# SparkX_smol_LiPo_Power.net
KiCad netlist of a schematic drawn in EAGLE
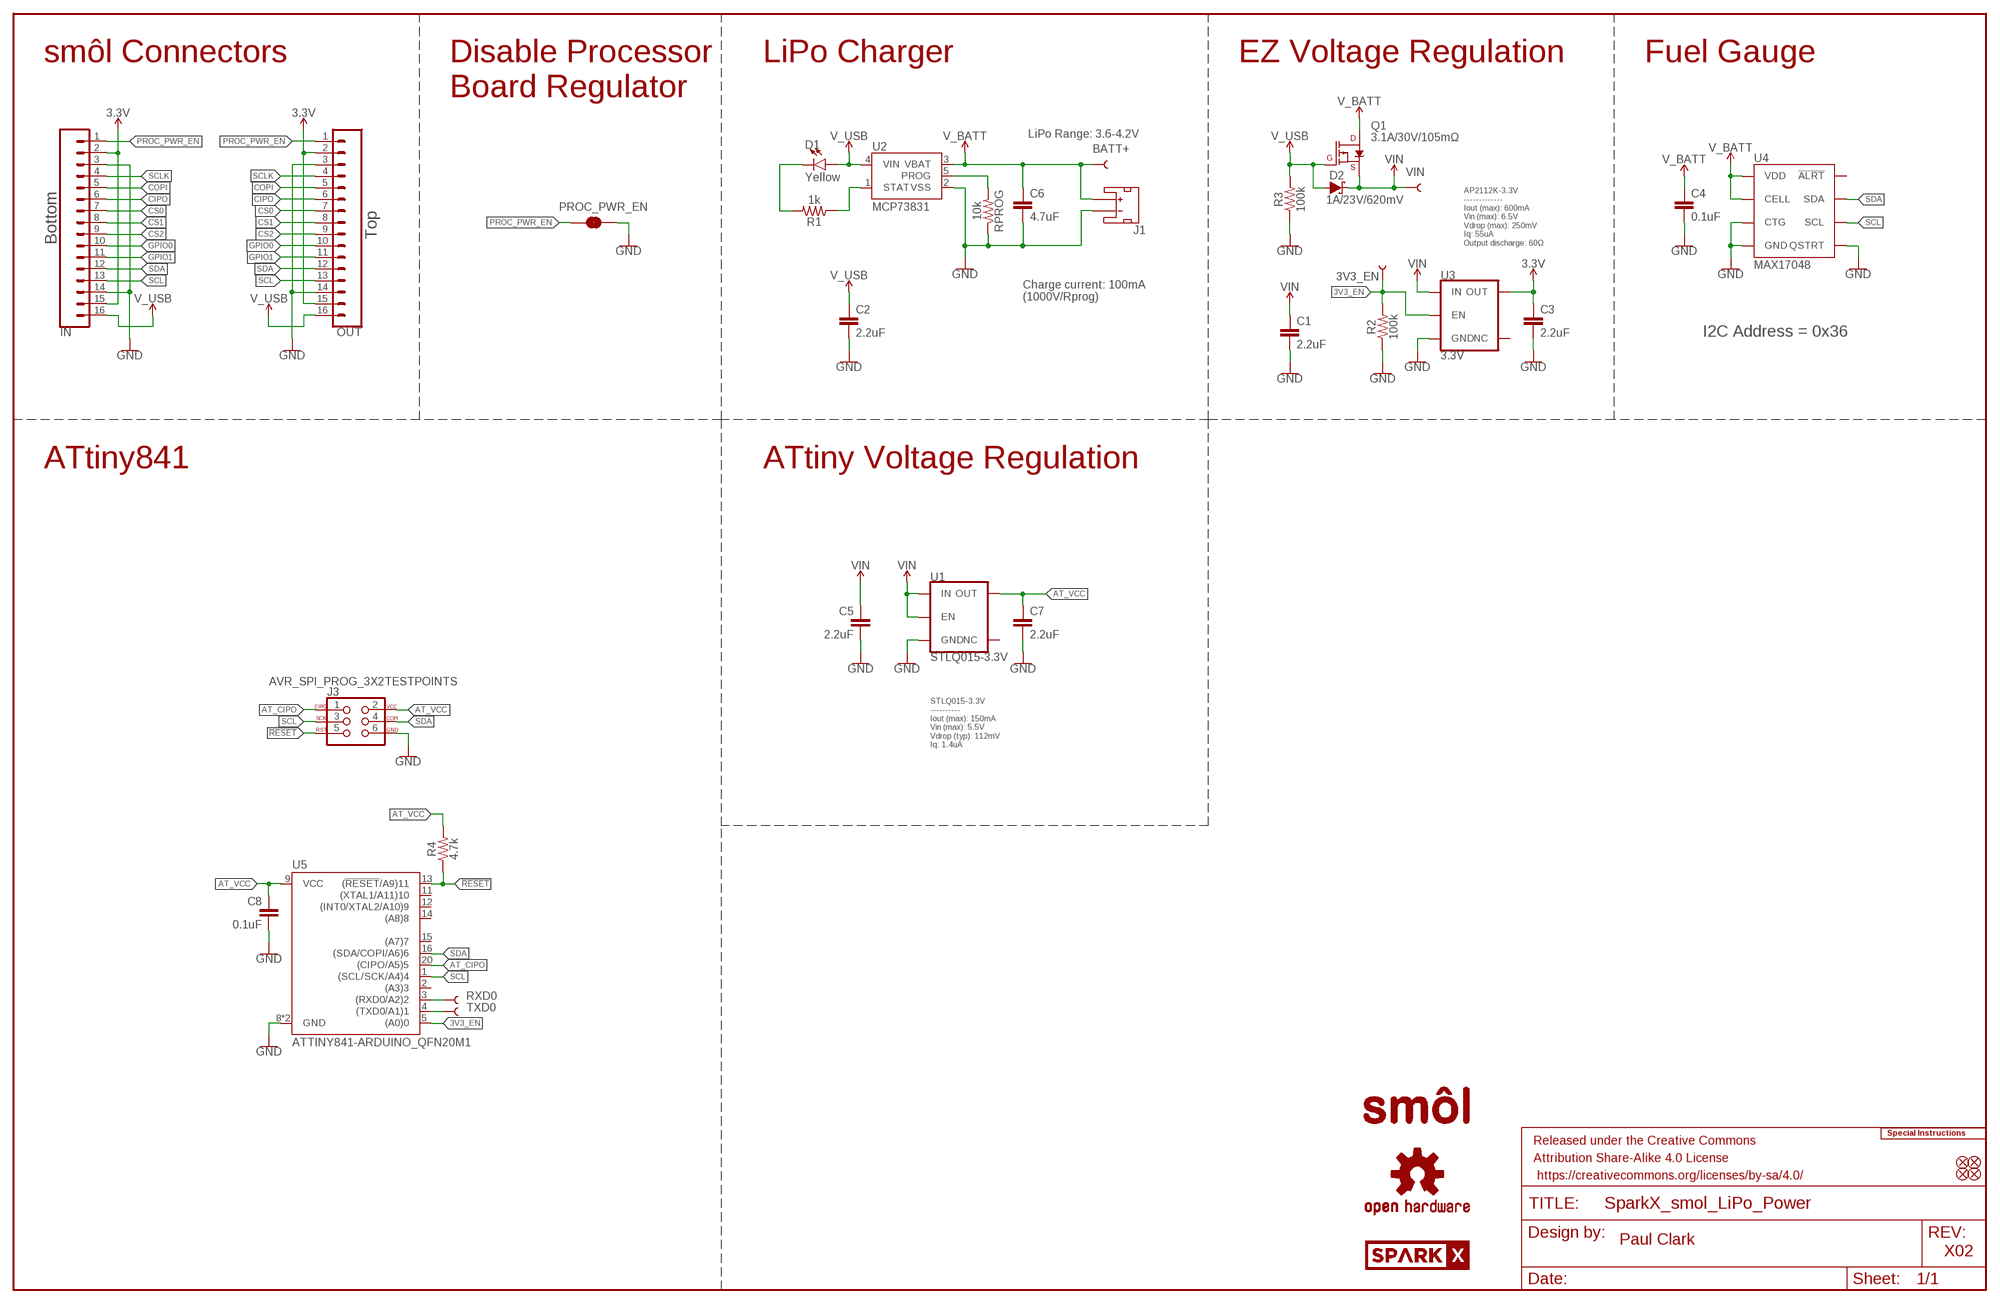
[diagram p0: schematic, sheet 1]

(export (version "E")
  (design (tool "Eeschema 10.0.6"))
  (components
    (comp (ref "3V3_EN")
      (value "TEST-POINT3X4")
      (footprint "eagle-import:PAD.03X.04")
      (libsource (lib "eagle-import") (part "TEST-POINT3X4"))
    )
    (comp (ref "BATT+")
      (value "TEST-POINT3X4")
      (footprint "eagle-import:PAD.03X.04")
      (libsource (lib "eagle-import") (part "TEST-POINT3X4"))
    )
    (comp (ref "C1")
      (value "2.2uF")
      (footprint "eagle-import:0402-TIGHT")
      (libsource (lib "eagle-import") (part "2.2UF-0402_TIGHT-10V-10%-X5R"))
    )
    (comp (ref "C2")
      (value "2.2uF")
      (footprint "eagle-import:0402-TIGHT")
      (libsource (lib "eagle-import") (part "2.2UF-0402_TIGHT-10V-10%-X5R"))
    )
    (comp (ref "C3")
      (value "2.2uF")
      (footprint "eagle-import:0402-TIGHT")
      (libsource (lib "eagle-import") (part "2.2UF-0402_TIGHT-10V-10%-X5R"))
    )
    (comp (ref "C4")
      (value "0.1uF")
      (footprint "eagle-import:0402-TIGHT")
      (libsource (lib "eagle-import") (part "0.1UF-0402T-6.3V-10%-X7R"))
    )
    (comp (ref "C5")
      (value "2.2uF")
      (footprint "eagle-import:0402-TIGHT")
      (libsource (lib "eagle-import") (part "2.2UF-0402_TIGHT-10V-10%-X5R"))
    )
    (comp (ref "C6")
      (value "4.7uF")
      (footprint "eagle-import:0402-TIGHT")
      (libsource (lib "eagle-import") (part "4.7UF-0402_TIGHT-6.3V-20%-X5R"))
    )
    (comp (ref "C7")
      (value "2.2uF")
      (footprint "eagle-import:0402-TIGHT")
      (libsource (lib "eagle-import") (part "2.2UF-0402_TIGHT-10V-10%-X5R"))
    )
    (comp (ref "C8")
      (value "0.1uF")
      (footprint "eagle-import:0402-TIGHT")
      (libsource (lib "eagle-import") (part "0.1UF-0402T-6.3V-10%-X7R"))
    )
    (comp (ref "D1")
      (value "Yellow")
      (footprint "eagle-import:LED-0603")
      (libsource (lib "eagle-import") (part "LED-YELLOW0603"))
    )
    (comp (ref "D2")
      (value "1A/23V/620mV")
      (footprint "eagle-import:SOD-323")
      (libsource (lib "eagle-import") (part "DIODE-SCHOTTKY-BAT20J"))
    )
    (comp (ref "FD1")
      (value "FIDUCIALUFIDUCIAL")
      (footprint "eagle-import:FIDUCIAL-MICRO")
      (libsource (lib "eagle-import") (part "FIDUCIALUFIDUCIAL"))
    )
    (comp (ref "FD2")
      (value "FIDUCIALUFIDUCIAL")
      (footprint "eagle-import:FIDUCIAL-MICRO")
      (libsource (lib "eagle-import") (part "FIDUCIALUFIDUCIAL"))
    )
    (comp (ref "FD3")
      (value "FIDUCIALUFIDUCIAL")
      (footprint "eagle-import:FIDUCIAL-MICRO")
      (libsource (lib "eagle-import") (part "FIDUCIALUFIDUCIAL"))
    )
    (comp (ref "FD4")
      (value "FIDUCIALUFIDUCIAL")
      (footprint "eagle-import:FIDUCIAL-MICRO")
      (libsource (lib "eagle-import") (part "FIDUCIALUFIDUCIAL"))
    )
    (comp (ref "FRAME1")
      (value "FRAME-LEDGER")
      (footprint "eagle-import:CREATIVE_COMMONS")
      (libsource (lib "eagle-import") (part "FRAME-LEDGER"))
    )
    (comp (ref "IN")
      (value "CONN_16FPC_16_0.5MM")
      (footprint "eagle-import:FPC_16_0.5MM")
      (libsource (lib "eagle-import") (part "CONN_16FPC_16_0.5MM"))
    )
    (comp (ref "J1")
      (value "JST_2MM_MALE")
      (footprint "eagle-import:JST-2-SMD")
      (libsource (lib "eagle-import") (part "JST_2MM_MALE"))
    )
    (comp (ref "J3")
      (value "AVR_SPI_PROG_3X2TESTPOINTS")
      (footprint "eagle-import:2X3_TEST_POINTS")
      (libsource (lib "eagle-import") (part "AVR_SPI_PROG_3X2TESTPOINTS"))
    )
    (comp (ref "LOGO1")
      (value "SPECIAL_INSTRUCTIONS-ORDERING")
      (footprint "eagle-import:ORDERING_INSTRUCTIONS")
      (libsource (lib "eagle-import") (part "SPECIAL_INSTRUCTIONS-ORDERING"))
    )
    (comp (ref "LOGO2")
      (value "OSHW-LOGOMINI")
      (footprint "eagle-import:OSHW-LOGO-MINI")
      (libsource (lib "eagle-import") (part "OSHW-LOGOMINI"))
    )
    (comp (ref "LOGO3")
      (value "OSHW-LOGOMINI")
      (footprint "eagle-import:OSHW-LOGO-MINI")
      (libsource (lib "eagle-import") (part "OSHW-LOGOMINI"))
    )
    (comp (ref "OUT")
      (value "CONN_16FPC_16_0.5MM")
      (footprint "eagle-import:FPC_16_0.5MM")
      (libsource (lib "eagle-import") (part "CONN_16FPC_16_0.5MM"))
    )
    (comp (ref "PROC_PWR_EN")
      (value "JUMPER-SMT_2_NC_TRACE_SILK")
      (footprint "eagle-import:SMT-JUMPER_2_NC_TRACE_SILK")
      (libsource (lib "eagle-import") (part "JUMPER-SMT_2_NC_TRACE_SILK"))
    )
    (comp (ref "Q1")
      (value "3.1A/30V/105mΩ")
      (footprint "eagle-import:SOT23-3")
      (libsource (lib "eagle-import") (part "MOSFET_PCH-DMG2307L"))
    )
    (comp (ref "R1")
      (value "1k")
      (footprint "eagle-import:0402-TIGHT")
      (libsource (lib "eagle-import") (part "1KOHM-0402T-1/16W-1%"))
    )
    (comp (ref "R2")
      (value "100k")
      (footprint "eagle-import:0402-TIGHT")
      (libsource (lib "eagle-import") (part "100KOHM-0402T-1/16W-1%"))
    )
    (comp (ref "R3")
      (value "100k")
      (footprint "eagle-import:0402-TIGHT")
      (libsource (lib "eagle-import") (part "100KOHM-0402T-1/16W-1%"))
    )
    (comp (ref "R4")
      (value "4.7k")
      (footprint "eagle-import:0402-TIGHT")
      (libsource (lib "eagle-import") (part "4.7KOHM-0402T-1/16W-1%"))
    )
    (comp (ref "RPROG")
      (value "10k")
      (footprint "eagle-import:0402-TIGHT")
      (libsource (lib "eagle-import") (part "10KOHM-0402T-1/16W-1%"))
    )
    (comp (ref "RXD0")
      (value "TEST-POINT3X4")
      (footprint "eagle-import:PAD.03X.04")
      (libsource (lib "eagle-import") (part "TEST-POINT3X4"))
    )
    (comp (ref "TXD0")
      (value "TEST-POINT3X4")
      (footprint "eagle-import:PAD.03X.04")
      (libsource (lib "eagle-import") (part "TEST-POINT3X4"))
    )
    (comp (ref "U$1")
      (value "SPARKX-LOGO3")
      (footprint "eagle-import:SPARKX-SMALL")
      (libsource (lib "eagle-import") (part "SPARKX-LOGO3"))
    )
    (comp (ref "U$3")
      (value "SMOL_LOGOSMALL")
      (footprint "eagle-import:SMOL_SMALL")
      (libsource (lib "eagle-import") (part "SMOL_LOGOSMALL"))
    )
    (comp (ref "U$9")
      (value "SMOL_LOGOSMALL")
      (footprint "eagle-import:SMOL_SMALL")
      (libsource (lib "eagle-import") (part "SMOL_LOGOSMALL"))
    )
    (comp (ref "U1")
      (value "STLQ015-3.3V")
      (footprint "eagle-import:SOT23-5")
      (libsource (lib "eagle-import") (part "STLQ015-3.3V"))
    )
    (comp (ref "U2")
      (value "MCP73831")
      (footprint "eagle-import:SOT23-5")
      (libsource (lib "eagle-import") (part "MCP73831"))
    )
    (comp (ref "U3")
      (value "3.3V")
      (footprint "eagle-import:SOT23-5")
      (libsource (lib "eagle-import") (part "V_REG_AP2112K-3.3V"))
    )
    (comp (ref "U4")
      (value "MAX17048")
      (footprint "eagle-import:DFN-8")
      (libsource (lib "eagle-import") (part "MAX17048DFN8"))
    )
    (comp (ref "U5")
      (value "ATTINY841-ARDUINO_QFN20M1")
      (footprint "eagle-import:QFN20_20M1")
      (fields (field (name "DIGIKEY_PART") "ATTINY841-MU-ND"))
      (libsource (lib "eagle-import") (part "ATTINY841-ARDUINO_QFN20M1"))
    )
    (comp (ref "VIN")
      (value "TEST-POINT3X4")
      (footprint "eagle-import:PAD.03X.04")
      (libsource (lib "eagle-import") (part "TEST-POINT3X4"))
    )
  )
  (nets
    (net (code "1") (name "/~{RESET}") (class "Default")
      (node (ref "J3") (pin "5") (pinfunction "5_5") (pintype "passive"))
      (node (ref "R4") (pin "1") (pinfunction "1_1") (pintype "passive"))
      (node (ref "U5") (pin "13") (pinfunction "(~{RESET}/A9)11_13") (pintype "bidirectional"))
    )
    (net (code "2") (name "3.3V") (class "Default")
      (node (ref "C3") (pin "1") (pinfunction "1_1") (pintype "passive"))
      (node (ref "IN") (pin "15") (pinfunction "15_15") (pintype "passive"))
      (node (ref "IN") (pin "2") (pinfunction "2_2") (pintype "passive"))
      (node (ref "OUT") (pin "15") (pinfunction "15_15") (pintype "passive"))
      (node (ref "OUT") (pin "2") (pinfunction "2_2") (pintype "passive"))
      (node (ref "U3") (pin "5") (pinfunction "OUT_5") (pintype "passive"))
    )
    (net (code "3") (name "3V3_EN") (class "Default")
      (node (ref "3V3_EN") (pin "1") (pinfunction "1_1") (pintype "bidirectional"))
      (node (ref "R2") (pin "2") (pinfunction "2_2") (pintype "passive"))
      (node (ref "U3") (pin "3") (pinfunction "EN_3") (pintype "input"))
      (node (ref "U5") (pin "5") (pinfunction "(A0)0_5") (pintype "bidirectional"))
    )
    (net (code "4") (name "AT_CIPO") (class "Default")
      (node (ref "J3") (pin "1") (pinfunction "1_1") (pintype "passive"))
      (node (ref "U5") (pin "20") (pinfunction "(CIPO/A5)5_20") (pintype "bidirectional"))
    )
    (net (code "5") (name "AT_VCC") (class "Default")
      (node (ref "C7") (pin "1") (pinfunction "1_1") (pintype "passive"))
      (node (ref "C8") (pin "1") (pinfunction "1_1") (pintype "passive"))
      (node (ref "J3") (pin "2") (pinfunction "2_2") (pintype "passive"))
      (node (ref "R4") (pin "2") (pinfunction "2_2") (pintype "passive"))
      (node (ref "U1") (pin "5") (pinfunction "OUT_5") (pintype "passive"))
      (node (ref "U5") (pin "9") (pinfunction "VCC_9") (pintype "power_in"))
    )
    (net (code "6") (name "CIPO") (class "Default")
      (node (ref "IN") (pin "6") (pinfunction "6_6") (pintype "passive"))
      (node (ref "OUT") (pin "6") (pinfunction "6_6") (pintype "passive"))
    )
    (net (code "7") (name "COPI") (class "Default")
      (node (ref "IN") (pin "5") (pinfunction "5_5") (pintype "passive"))
      (node (ref "OUT") (pin "5") (pinfunction "5_5") (pintype "passive"))
    )
    (net (code "8") (name "CS0") (class "Default")
      (node (ref "IN") (pin "7") (pinfunction "7_7") (pintype "passive"))
      (node (ref "OUT") (pin "7") (pinfunction "7_7") (pintype "passive"))
    )
    (net (code "9") (name "CS1") (class "Default")
      (node (ref "IN") (pin "8") (pinfunction "8_8") (pintype "passive"))
      (node (ref "OUT") (pin "8") (pinfunction "8_8") (pintype "passive"))
    )
    (net (code "10") (name "CS2") (class "Default")
      (node (ref "IN") (pin "9") (pinfunction "9_9") (pintype "passive"))
      (node (ref "OUT") (pin "9") (pinfunction "9_9") (pintype "passive"))
    )
    (net (code "11") (name "GND") (class "Default")
      (node (ref "C1") (pin "2") (pinfunction "2_2") (pintype "passive"))
      (node (ref "C2") (pin "2") (pinfunction "2_2") (pintype "passive"))
      (node (ref "C3") (pin "2") (pinfunction "2_2") (pintype "passive"))
      (node (ref "C4") (pin "2") (pinfunction "2_2") (pintype "passive"))
      (node (ref "C5") (pin "2") (pinfunction "2_2") (pintype "passive"))
      (node (ref "C6") (pin "2") (pinfunction "2_2") (pintype "passive"))
      (node (ref "C7") (pin "2") (pinfunction "2_2") (pintype "passive"))
      (node (ref "C8") (pin "2") (pinfunction "2_2") (pintype "passive"))
      (node (ref "IN") (pin "14") (pinfunction "14_14") (pintype "passive"))
      (node (ref "IN") (pin "3") (pinfunction "3_3") (pintype "passive"))
      (node (ref "J1") (pin "1") (pinfunction "-_1") (pintype "bidirectional"))
      (node (ref "J3") (pin "6") (pinfunction "6_6") (pintype "passive"))
      (node (ref "OUT") (pin "14") (pinfunction "14_14") (pintype "passive"))
      (node (ref "OUT") (pin "3") (pinfunction "3_3") (pintype "passive"))
      (node (ref "PROC_PWR_EN") (pin "2") (pinfunction "2_2") (pintype "passive"))
      (node (ref "R2") (pin "1") (pinfunction "1_1") (pintype "passive"))
      (node (ref "R3") (pin "1") (pinfunction "1_1") (pintype "passive"))
      (node (ref "RPROG") (pin "1") (pinfunction "1_1") (pintype "passive"))
      (node (ref "U1") (pin "2") (pinfunction "GND_2") (pintype "input"))
      (node (ref "U2") (pin "2") (pinfunction "VSS_2") (pintype "power_in"))
      (node (ref "U3") (pin "2") (pinfunction "GND_2") (pintype "input"))
      (node (ref "U4") (pin "1") (pinfunction "CTG_1") (pintype "input"))
      (node (ref "U4") (pin "4") (pinfunction "GND_4") (pintype "bidirectional"))
      (node (ref "U4") (pin "6") (pinfunction "QSTRT_6") (pintype "bidirectional"))
      (node (ref "U4") (pin "9") (pinfunction "GND_9") (pintype "bidirectional"))
      (node (ref "U5") (pin "8") (pinfunction "GND_8") (pintype "power_in"))
      (node (ref "U5") (pin "PAD") (pinfunction "GND_PAD") (pintype "power_in"))
    )
    (net (code "12") (name "GPIO0") (class "Default")
      (node (ref "IN") (pin "10") (pinfunction "10_10") (pintype "passive"))
      (node (ref "OUT") (pin "10") (pinfunction "10_10") (pintype "passive"))
    )
    (net (code "13") (name "GPIO1") (class "Default")
      (node (ref "IN") (pin "11") (pinfunction "11_11") (pintype "passive"))
      (node (ref "OUT") (pin "11") (pinfunction "11_11") (pintype "passive"))
    )
    (net (code "14") (name "Net-(D1-PadC)") (class "Default")
      (node (ref "D1") (pin "C") (pinfunction "C_C") (pintype "passive"))
      (node (ref "R1") (pin "2") (pinfunction "2_2") (pintype "passive"))
    )
    (net (code "15") (name "Net-(U2-PROG)") (class "Default")
      (node (ref "RPROG") (pin "2") (pinfunction "2_2") (pintype "passive"))
      (node (ref "U2") (pin "5") (pinfunction "PROG_5") (pintype "input"))
    )
    (net (code "16") (name "Net-(U2-STAT)") (class "Default")
      (node (ref "R1") (pin "1") (pinfunction "1_1") (pintype "passive"))
      (node (ref "U2") (pin "1") (pinfunction "STAT_1") (pintype "output"))
    )
    (net (code "17") (name "Net-(U5-(RXD0{slash}A2)2)") (class "Default")
      (node (ref "RXD0") (pin "1") (pinfunction "1_1") (pintype "bidirectional"))
      (node (ref "U5") (pin "3") (pinfunction "(RXD0/A2)2_3") (pintype "bidirectional"))
    )
    (net (code "18") (name "Net-(U5-(TXD0{slash}A1)1)") (class "Default")
      (node (ref "TXD0") (pin "1") (pinfunction "1_1") (pintype "bidirectional"))
      (node (ref "U5") (pin "4") (pinfunction "(TXD0/A1)1_4") (pintype "bidirectional"))
    )
    (net (code "19") (name "PROC_PWR_EN") (class "Default")
      (node (ref "IN") (pin "1") (pinfunction "1_1") (pintype "passive"))
      (node (ref "OUT") (pin "1") (pinfunction "1_1") (pintype "passive"))
      (node (ref "PROC_PWR_EN") (pin "1") (pinfunction "1_1") (pintype "passive"))
    )
    (net (code "20") (name "SCL") (class "Default")
      (node (ref "IN") (pin "13") (pinfunction "13_13") (pintype "passive"))
      (node (ref "J3") (pin "3") (pinfunction "3_3") (pintype "passive"))
      (node (ref "OUT") (pin "13") (pinfunction "13_13") (pintype "passive"))
      (node (ref "U4") (pin "7") (pinfunction "SCL_7") (pintype "output"))
      (node (ref "U5") (pin "1") (pinfunction "(SCL/SCK/A4)4_1") (pintype "bidirectional"))
    )
    (net (code "21") (name "SCLK") (class "Default")
      (node (ref "IN") (pin "4") (pinfunction "4_4") (pintype "passive"))
      (node (ref "OUT") (pin "4") (pinfunction "4_4") (pintype "passive"))
    )
    (net (code "22") (name "SDA") (class "Default")
      (node (ref "IN") (pin "12") (pinfunction "12_12") (pintype "passive"))
      (node (ref "J3") (pin "4") (pinfunction "4_4") (pintype "passive"))
      (node (ref "OUT") (pin "12") (pinfunction "12_12") (pintype "passive"))
      (node (ref "U4") (pin "8") (pinfunction "SDA_8") (pintype "input"))
      (node (ref "U5") (pin "16") (pinfunction "(SDA/COPI/A6)6_16") (pintype "bidirectional"))
    )
    (net (code "23") (name "VIN") (class "Default")
      (node (ref "C1") (pin "1") (pinfunction "1_1") (pintype "passive"))
      (node (ref "C5") (pin "1") (pinfunction "1_1") (pintype "passive"))
      (node (ref "D2") (pin "C") (pinfunction "C_C") (pintype "passive"))
      (node (ref "Q1") (pin "2") (pinfunction "S_2") (pintype "bidirectional"))
      (node (ref "U1") (pin "1") (pinfunction "IN_1") (pintype "input"))
      (node (ref "U1") (pin "3") (pinfunction "EN_3") (pintype "input"))
      (node (ref "U3") (pin "1") (pinfunction "IN_1") (pintype "input"))
      (node (ref "VIN") (pin "1") (pinfunction "1_1") (pintype "bidirectional"))
    )
    (net (code "24") (name "V_BATT") (class "Default")
      (node (ref "BATT+") (pin "1") (pinfunction "1_1") (pintype "bidirectional"))
      (node (ref "C4") (pin "1") (pinfunction "1_1") (pintype "passive"))
      (node (ref "C6") (pin "1") (pinfunction "1_1") (pintype "passive"))
      (node (ref "J1") (pin "2") (pinfunction "+_2") (pintype "bidirectional"))
      (node (ref "Q1") (pin "3") (pinfunction "D_3") (pintype "bidirectional"))
      (node (ref "U2") (pin "3") (pinfunction "VBAT_3") (pintype "power_in"))
      (node (ref "U4") (pin "2") (pinfunction "CELL_2") (pintype "input"))
      (node (ref "U4") (pin "3") (pinfunction "VDD_3") (pintype "bidirectional"))
    )
    (net (code "25") (name "V_USB") (class "Default")
      (node (ref "C2") (pin "1") (pinfunction "1_1") (pintype "passive"))
      (node (ref "D1") (pin "A") (pinfunction "A_A") (pintype "passive"))
      (node (ref "D2") (pin "A") (pinfunction "A_A") (pintype "passive"))
      (node (ref "IN") (pin "16") (pinfunction "16_16") (pintype "passive"))
      (node (ref "OUT") (pin "16") (pinfunction "16_16") (pintype "passive"))
      (node (ref "Q1") (pin "1") (pinfunction "G_1") (pintype "bidirectional"))
      (node (ref "R3") (pin "2") (pinfunction "2_2") (pintype "passive"))
      (node (ref "U2") (pin "4") (pinfunction "VIN_4") (pintype "power_in"))
    )
    (net (code "26") (name "unconnected-(J1-PAD1-PadNC1)") (class "Default")
      (node (ref "J1") (pin "NC1") (pinfunction "PAD1_NC1") (pintype "bidirectional"))
    )
    (net (code "27") (name "unconnected-(J1-PAD2-PadNC2)") (class "Default")
      (node (ref "J1") (pin "NC2") (pinfunction "PAD2_NC2") (pintype "bidirectional"))
    )
    (net (code "28") (name "unconnected-(U1-NC-Pad4)") (class "Default")
      (node (ref "U1") (pin "4") (pinfunction "NC_4") (pintype "no_connect"))
    )
    (net (code "29") (name "unconnected-(U3-NC-Pad4)") (class "Default")
      (node (ref "U3") (pin "4") (pinfunction "NC_4") (pintype "no_connect"))
    )
    (net (code "30") (name "unconnected-(U4-~{ALRT}-Pad5)") (class "Default")
      (node (ref "U4") (pin "5") (pinfunction "~{ALRT}_5") (pintype "bidirectional"))
    )
    (net (code "31") (name "unconnected-(U5-(A3)3-Pad2)") (class "Default")
      (node (ref "U5") (pin "2") (pinfunction "(A3)3_2") (pintype "bidirectional"))
    )
    (net (code "32") (name "unconnected-(U5-(A7)7-Pad15)") (class "Default")
      (node (ref "U5") (pin "15") (pinfunction "(A7)7_15") (pintype "bidirectional"))
    )
    (net (code "33") (name "unconnected-(U5-(A8)8-Pad14)") (class "Default")
      (node (ref "U5") (pin "14") (pinfunction "(A8)8_14") (pintype "bidirectional"))
    )
    (net (code "34") (name "unconnected-(U5-(INT0{slash}XTAL2{slash}A10)9-Pad12)") (class "Default")
      (node (ref "U5") (pin "12") (pinfunction "(INT0/XTAL2/A10)9_12") (pintype "bidirectional"))
    )
    (net (code "35") (name "unconnected-(U5-(XTAL1{slash}A11)10-Pad11)") (class "Default")
      (node (ref "U5") (pin "11") (pinfunction "(XTAL1/A11)10_11") (pintype "bidirectional"))
    )
  )
)
